# Led_sequencer.net
KiCad netlist of a schematic drawn in Altium Designer
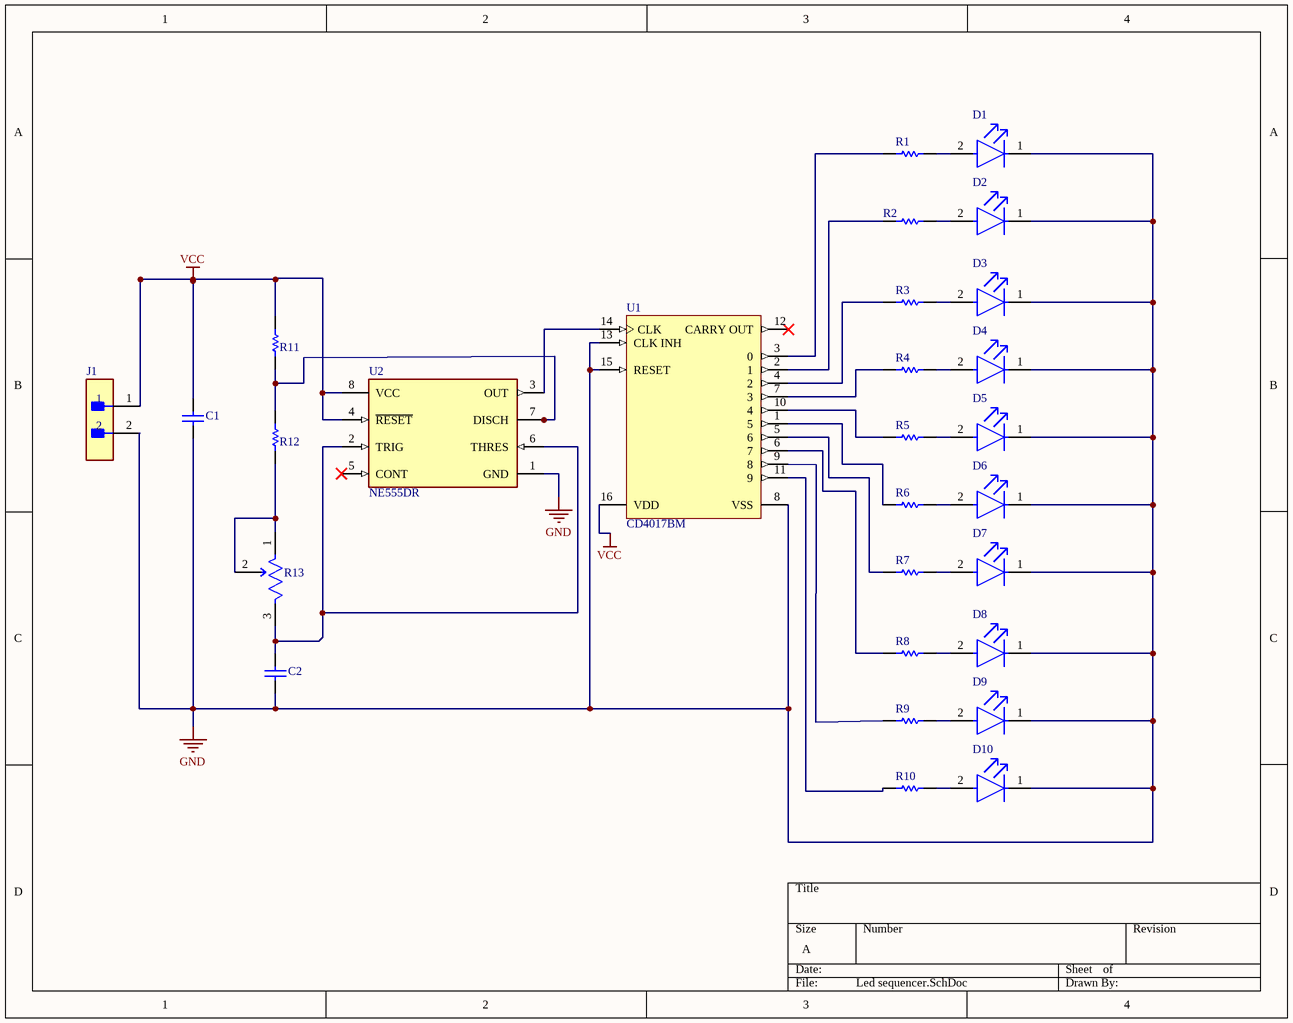
[diagram p0: Led sequencer.SchDoc]

(export (version "E")
  (design (tool "Eeschema 10.0.6"))
  (components
    (comp (ref "C1")
      (value "1uf")
      (footprint "CAPC2013X135X45LL10T25")
      (fields (field (name "MANUFACTURER") "Murata") (field (name "PART NUMBER") "GRM21BR71H105KA12L"))
      (libsource (lib "Altium Content Vault") (part "CAP"))
    )
    (comp (ref "C2")
      (value "1uf")
      (footprint "CAPC2013X135X45LL10T25")
      (fields (field (name "MANUFACTURER") "Murata") (field (name "PART NUMBER") "GRM21BR71H105KA12L"))
      (libsource (lib "Altium Content Vault") (part "CAP"))
    )
    (comp (ref "D1")
      (value "HLMP-1719")
      (footprint "FP-HLMP-1719-MFG")
      (description "LED Uni-Color Yellow 2-Pin T-1")
      (fields (field (name "MANUFACTURER") "Broadcom"))
      (libsource (lib "Altium Content Vault") (part "8706943c75ba83719d021d2fdc84c58"))
    )
    (comp (ref "D2")
      (value "HLMP-1719")
      (footprint "FP-HLMP-1719-MFG")
      (description "LED Uni-Color Yellow 2-Pin T-1")
      (fields (field (name "MANUFACTURER") "Broadcom"))
      (libsource (lib "Altium Content Vault") (part "8706943c75ba83719d021d2fdc84c58"))
    )
    (comp (ref "D3")
      (value "HLMP-1719")
      (footprint "FP-HLMP-1719-MFG")
      (description "LED Uni-Color Yellow 2-Pin T-1")
      (fields (field (name "MANUFACTURER") "Broadcom"))
      (libsource (lib "Altium Content Vault") (part "8706943c75ba83719d021d2fdc84c58"))
    )
    (comp (ref "D4")
      (value "HLMP-1719")
      (footprint "FP-HLMP-1719-MFG")
      (description "LED Uni-Color Yellow 2-Pin T-1")
      (fields (field (name "MANUFACTURER") "Broadcom"))
      (libsource (lib "Altium Content Vault") (part "8706943c75ba83719d021d2fdc84c58"))
    )
    (comp (ref "D5")
      (value "HLMP-1719")
      (footprint "FP-HLMP-1719-MFG")
      (description "LED Uni-Color Yellow 2-Pin T-1")
      (fields (field (name "MANUFACTURER") "Broadcom"))
      (libsource (lib "Altium Content Vault") (part "8706943c75ba83719d021d2fdc84c58"))
    )
    (comp (ref "D6")
      (value "HLMP-1719")
      (footprint "FP-HLMP-1719-MFG")
      (description "LED Uni-Color Yellow 2-Pin T-1")
      (fields (field (name "MANUFACTURER") "Broadcom"))
      (libsource (lib "Altium Content Vault") (part "8706943c75ba83719d021d2fdc84c58"))
    )
    (comp (ref "D7")
      (value "HLMP-1719")
      (footprint "FP-HLMP-1719-MFG")
      (description "LED Uni-Color Yellow 2-Pin T-1")
      (fields (field (name "MANUFACTURER") "Broadcom"))
      (libsource (lib "Altium Content Vault") (part "8706943c75ba83719d021d2fdc84c58"))
    )
    (comp (ref "D8")
      (value "HLMP-1719")
      (footprint "FP-HLMP-1719-MFG")
      (description "LED Uni-Color Yellow 2-Pin T-1")
      (fields (field (name "MANUFACTURER") "Broadcom"))
      (libsource (lib "Altium Content Vault") (part "8706943c75ba83719d021d2fdc84c58"))
    )
    (comp (ref "D9")
      (value "HLMP-1719")
      (footprint "FP-HLMP-1719-MFG")
      (description "LED Uni-Color Yellow 2-Pin T-1")
      (fields (field (name "MANUFACTURER") "Broadcom"))
      (libsource (lib "Altium Content Vault") (part "8706943c75ba83719d021d2fdc84c58"))
    )
    (comp (ref "D10")
      (value "HLMP-1719")
      (footprint "FP-HLMP-1719-MFG")
      (description "LED Uni-Color Yellow 2-Pin T-1")
      (fields (field (name "MANUFACTURER") "Broadcom"))
      (libsource (lib "Altium Content Vault") (part "8706943c75ba83719d021d2fdc84c58"))
    )
    (comp (ref "J1")
      (value "M20-9990246")
      (footprint "FP-M20-9990246-MFG")
      (description "Connector Header Through Hole 2 position 0.100\" (2.54mm)")
      (fields (field (name "OCTOPART") "https://octopart.com/m20-9990246-harwin-2590635"))
      (libsource (lib "Altium Content Vault") (part "3bc925449376181038e59eaffc5286c"))
    )
    (comp (ref "R1")
      (value "1k")
      (footprint "RESC2013X60X35ML10T20")
      (description "Chip Resistor, 1 KOhm, +/- 1%, 125 mW, -55 to 155 degC, 0805 (2012 Metric), RoHS, Tape and Reel")
      (fields (field (name "TOLERANCE") "1%") (field (name "MANUFACTURER") "Yageo"))
      (libsource (lib "Altium Content Vault") (part "RES-2"))
    )
    (comp (ref "R2")
      (value "1k")
      (footprint "RESC2013X60X35ML10T20")
      (description "Chip Resistor, 1 KOhm, +/- 1%, 125 mW, -55 to 155 degC, 0805 (2012 Metric), RoHS, Tape and Reel")
      (fields (field (name "TOLERANCE") "1%") (field (name "MANUFACTURER") "Yageo"))
      (libsource (lib "Altium Content Vault") (part "RES-2"))
    )
    (comp (ref "R3")
      (value "1k")
      (footprint "RESC2013X60X35ML10T20")
      (description "Chip Resistor, 1 KOhm, +/- 1%, 125 mW, -55 to 155 degC, 0805 (2012 Metric), RoHS, Tape and Reel")
      (fields (field (name "TOLERANCE") "1%") (field (name "MANUFACTURER") "Yageo"))
      (libsource (lib "Altium Content Vault") (part "RES-2"))
    )
    (comp (ref "R4")
      (value "1k")
      (footprint "RESC2013X60X35ML10T20")
      (description "Chip Resistor, 1 KOhm, +/- 1%, 125 mW, -55 to 155 degC, 0805 (2012 Metric), RoHS, Tape and Reel")
      (fields (field (name "TOLERANCE") "1%") (field (name "MANUFACTURER") "Yageo"))
      (libsource (lib "Altium Content Vault") (part "RES-2"))
    )
    (comp (ref "R5")
      (value "1k")
      (footprint "RESC2013X60X35ML10T20")
      (description "Chip Resistor, 1 KOhm, +/- 1%, 125 mW, -55 to 155 degC, 0805 (2012 Metric), RoHS, Tape and Reel")
      (fields (field (name "TOLERANCE") "1%") (field (name "MANUFACTURER") "Yageo"))
      (libsource (lib "Altium Content Vault") (part "RES-2"))
    )
    (comp (ref "R6")
      (value "1k")
      (footprint "RESC2013X60X35ML10T20")
      (description "Chip Resistor, 1 KOhm, +/- 1%, 125 mW, -55 to 155 degC, 0805 (2012 Metric), RoHS, Tape and Reel")
      (fields (field (name "TOLERANCE") "1%") (field (name "MANUFACTURER") "Yageo"))
      (libsource (lib "Altium Content Vault") (part "RES-2"))
    )
    (comp (ref "R7")
      (value "1k")
      (footprint "RESC2013X60X35ML10T20")
      (description "Chip Resistor, 1 KOhm, +/- 1%, 125 mW, -55 to 155 degC, 0805 (2012 Metric), RoHS, Tape and Reel")
      (fields (field (name "TOLERANCE") "1%") (field (name "MANUFACTURER") "Yageo"))
      (libsource (lib "Altium Content Vault") (part "RES-2"))
    )
    (comp (ref "R8")
      (value "1k")
      (footprint "RESC2013X60X35ML10T20")
      (description "Chip Resistor, 1 KOhm, +/- 1%, 125 mW, -55 to 155 degC, 0805 (2012 Metric), RoHS, Tape and Reel")
      (fields (field (name "TOLERANCE") "1%") (field (name "MANUFACTURER") "Yageo"))
      (libsource (lib "Altium Content Vault") (part "RES-2"))
    )
    (comp (ref "R9")
      (value "1k")
      (footprint "RESC2013X60X35ML10T20")
      (description "Chip Resistor, 1 KOhm, +/- 1%, 125 mW, -55 to 155 degC, 0805 (2012 Metric), RoHS, Tape and Reel")
      (fields (field (name "TOLERANCE") "1%") (field (name "MANUFACTURER") "Yageo"))
      (libsource (lib "Altium Content Vault") (part "RES-2"))
    )
    (comp (ref "R10")
      (value "1k")
      (footprint "RESC2013X60X35ML10T20")
      (description "Chip Resistor, 1 KOhm, +/- 1%, 125 mW, -55 to 155 degC, 0805 (2012 Metric), RoHS, Tape and Reel")
      (fields (field (name "TOLERANCE") "1%") (field (name "MANUFACTURER") "Yageo"))
      (libsource (lib "Altium Content Vault") (part "RES-2"))
    )
    (comp (ref "R11")
      (value "2.2k")
      (footprint "RESC2013X60X35ML10T20")
      (description "Chip Resistor, 1 KOhm, +/- 1%, 125 mW, -55 to 155 degC, 0805 (2012 Metric), RoHS, Tape and Reel")
      (fields (field (name "TOLERANCE") "1%") (field (name "MANUFACTURER") "Yageo"))
      (libsource (lib "Altium Content Vault") (part "RES-2"))
    )
    (comp (ref "R12")
      (value "10k")
      (footprint "RESC2013X60X35ML10T20")
      (description "Chip Resistor, 1 KOhm, +/- 1%, 125 mW, -55 to 155 degC, 0805 (2012 Metric), RoHS, Tape and Reel")
      (fields (field (name "TOLERANCE") "1%") (field (name "MANUFACTURER") "Yageo"))
      (libsource (lib "Altium Content Vault") (part "RES-2"))
    )
    (comp (ref "R13")
      (value "50k")
      (footprint "FP-3386P-MFG")
      (description "TRIMMER 100K OHM 0.5W PC PIN TOP")
      (fields (field (name "TOLERANCE") "10%"))
      (libsource (lib "Altium Content Vault") (part "13357d81287629c2fd191d242cfa50c"))
    )
    (comp (ref "U1")
      (value "CD4017BM")
      (footprint "D0016A_N")
      (description "CMOS Decade Counter with 10 Decoded Outputs, D0016A, TUBE")
      (fields
        (field (name "GENERIC PART NUMBER") "CD4017B")
        (field (name "MANUFACTURER") "Texas Instruments")
      )
      (libsource (lib "Altium Content Vault") (part "TI-CD4017B-16"))
    )
    (comp (ref "U2")
      (value "NE555DR")
      (footprint "FP-D0008A-IPC_A")
      (description "IC OSC SGL TIMER 100KHZ 8-SOIC")
      (libsource (lib "Altium Content Vault") (part "a29bba90211dec1890110b94dad7d53"))
    )
  )
  (nets
    (net (code "1") (name "GND") (class "Default")
      (node (ref "C1") (pin "1") (pinfunction "1_1") (pintype "passive"))
      (node (ref "C2") (pin "1") (pinfunction "1_1") (pintype "passive"))
      (node (ref "D1") (pin "1") (pinfunction "C_1") (pintype "passive"))
      (node (ref "D10") (pin "1") (pinfunction "C_1") (pintype "passive"))
      (node (ref "D2") (pin "1") (pinfunction "C_1") (pintype "passive"))
      (node (ref "D3") (pin "1") (pinfunction "C_1") (pintype "passive"))
      (node (ref "D4") (pin "1") (pinfunction "C_1") (pintype "passive"))
      (node (ref "D5") (pin "1") (pinfunction "C_1") (pintype "passive"))
      (node (ref "D6") (pin "1") (pinfunction "C_1") (pintype "passive"))
      (node (ref "D7") (pin "1") (pinfunction "C_1") (pintype "passive"))
      (node (ref "D8") (pin "1") (pinfunction "C_1") (pintype "passive"))
      (node (ref "D9") (pin "1") (pinfunction "C_1") (pintype "passive"))
      (node (ref "J1") (pin "2") (pinfunction "2_2") (pintype "passive"))
      (node (ref "U1") (pin "13") (pinfunction "CLK_INH_13") (pintype "input"))
      (node (ref "U1") (pin "15") (pinfunction "RESET_15") (pintype "input"))
      (node (ref "U1") (pin "8") (pinfunction "VSS_8") (pintype "power_in"))
      (node (ref "U2") (pin "1") (pinfunction "GND_1") (pintype "power_in"))
    )
    (net (code "2") (name "Net-(D1-A)") (class "Default")
      (node (ref "D1") (pin "2") (pinfunction "A_2") (pintype "passive"))
      (node (ref "R1") (pin "2") (pinfunction "2_2") (pintype "passive"))
    )
    (net (code "3") (name "Net-(D2-A)") (class "Default")
      (node (ref "D2") (pin "2") (pinfunction "A_2") (pintype "passive"))
      (node (ref "R2") (pin "2") (pinfunction "2_2") (pintype "passive"))
    )
    (net (code "4") (name "Net-(D3-A)") (class "Default")
      (node (ref "D3") (pin "2") (pinfunction "A_2") (pintype "passive"))
      (node (ref "R3") (pin "2") (pinfunction "2_2") (pintype "passive"))
    )
    (net (code "5") (name "Net-(D4-A)") (class "Default")
      (node (ref "D4") (pin "2") (pinfunction "A_2") (pintype "passive"))
      (node (ref "R4") (pin "2") (pinfunction "2_2") (pintype "passive"))
    )
    (net (code "6") (name "Net-(D5-A)") (class "Default")
      (node (ref "D5") (pin "2") (pinfunction "A_2") (pintype "passive"))
      (node (ref "R5") (pin "2") (pinfunction "2_2") (pintype "passive"))
    )
    (net (code "7") (name "Net-(D6-A)") (class "Default")
      (node (ref "D6") (pin "2") (pinfunction "A_2") (pintype "passive"))
      (node (ref "R6") (pin "2") (pinfunction "2_2") (pintype "passive"))
    )
    (net (code "8") (name "Net-(D7-A)") (class "Default")
      (node (ref "D7") (pin "2") (pinfunction "A_2") (pintype "passive"))
      (node (ref "R7") (pin "2") (pinfunction "2_2") (pintype "passive"))
    )
    (net (code "9") (name "Net-(D8-A)") (class "Default")
      (node (ref "D8") (pin "2") (pinfunction "A_2") (pintype "passive"))
      (node (ref "R8") (pin "2") (pinfunction "2_2") (pintype "passive"))
    )
    (net (code "10") (name "Net-(D9-A)") (class "Default")
      (node (ref "D9") (pin "2") (pinfunction "A_2") (pintype "passive"))
      (node (ref "R9") (pin "2") (pinfunction "2_2") (pintype "passive"))
    )
    (net (code "11") (name "Net-(D10-A)") (class "Default")
      (node (ref "D10") (pin "2") (pinfunction "A_2") (pintype "passive"))
      (node (ref "R10") (pin "2") (pinfunction "2_2") (pintype "passive"))
    )
    (net (code "12") (name "Net-(R13-CCW)") (class "Default")
      (node (ref "R12") (pin "1") (pinfunction "1_1") (pintype "passive"))
      (node (ref "R13") (pin "1") (pinfunction "CCW_1") (pintype "passive"))
      (node (ref "R13") (pin "2") (pinfunction "WIPER_2") (pintype "passive"))
    )
    (net (code "13") (name "Net-(R13-CW)") (class "Default")
      (node (ref "C2") (pin "2") (pinfunction "2_2") (pintype "passive"))
      (node (ref "R13") (pin "3") (pinfunction "CW_3") (pintype "passive"))
      (node (ref "U2") (pin "2") (pinfunction "TRIG_2") (pintype "input"))
      (node (ref "U2") (pin "6") (pinfunction "THRES_6") (pintype "input"))
    )
    (net (code "14") (name "Net-(U1-0)") (class "Default")
      (node (ref "R1") (pin "1") (pinfunction "1_1") (pintype "passive"))
      (node (ref "U1") (pin "3") (pinfunction "0_3") (pintype "output"))
    )
    (net (code "15") (name "Net-(U1-1)") (class "Default")
      (node (ref "R2") (pin "1") (pinfunction "1_1") (pintype "passive"))
      (node (ref "U1") (pin "2") (pinfunction "1_2") (pintype "output"))
    )
    (net (code "16") (name "Net-(U1-2)") (class "Default")
      (node (ref "R3") (pin "1") (pinfunction "1_1") (pintype "passive"))
      (node (ref "U1") (pin "4") (pinfunction "2_4") (pintype "output"))
    )
    (net (code "17") (name "Net-(U1-3)") (class "Default")
      (node (ref "R4") (pin "1") (pinfunction "1_1") (pintype "passive"))
      (node (ref "U1") (pin "7") (pinfunction "3_7") (pintype "output"))
    )
    (net (code "18") (name "Net-(U1-4)") (class "Default")
      (node (ref "R5") (pin "1") (pinfunction "1_1") (pintype "passive"))
      (node (ref "U1") (pin "10") (pinfunction "4_10") (pintype "output"))
    )
    (net (code "19") (name "Net-(U1-5)") (class "Default")
      (node (ref "R6") (pin "1") (pinfunction "1_1") (pintype "passive"))
      (node (ref "U1") (pin "1") (pinfunction "5_1") (pintype "output"))
    )
    (net (code "20") (name "Net-(U1-6)") (class "Default")
      (node (ref "R7") (pin "1") (pinfunction "1_1") (pintype "passive"))
      (node (ref "U1") (pin "5") (pinfunction "6_5") (pintype "output"))
    )
    (net (code "21") (name "Net-(U1-7)") (class "Default")
      (node (ref "R8") (pin "1") (pinfunction "1_1") (pintype "passive"))
      (node (ref "U1") (pin "6") (pinfunction "7_6") (pintype "output"))
    )
    (net (code "22") (name "Net-(U1-8)") (class "Default")
      (node (ref "R9") (pin "1") (pinfunction "1_1") (pintype "passive"))
      (node (ref "U1") (pin "9") (pinfunction "8_9") (pintype "output"))
    )
    (net (code "23") (name "Net-(U1-9)") (class "Default")
      (node (ref "R10") (pin "1") (pinfunction "1_1") (pintype "passive"))
      (node (ref "U1") (pin "11") (pinfunction "9_11") (pintype "output"))
    )
    (net (code "24") (name "Net-(U1-CLK)") (class "Default")
      (node (ref "U1") (pin "14") (pinfunction "CLK_14") (pintype "input"))
      (node (ref "U2") (pin "3") (pinfunction "OUT_3") (pintype "output"))
    )
    (net (code "25") (name "Net-(U2-DISCH)") (class "Default")
      (node (ref "R11") (pin "1") (pinfunction "1_1") (pintype "passive"))
      (node (ref "R12") (pin "2") (pinfunction "2_2") (pintype "passive"))
      (node (ref "U2") (pin "7") (pinfunction "DISCH_7") (pintype "open_collector"))
    )
    (net (code "26") (name "VCC") (class "Default")
      (node (ref "C1") (pin "2") (pinfunction "2_2") (pintype "passive"))
      (node (ref "J1") (pin "1") (pinfunction "1_1") (pintype "passive"))
      (node (ref "R11") (pin "2") (pinfunction "2_2") (pintype "passive"))
      (node (ref "U1") (pin "16") (pinfunction "VDD_16") (pintype "power_in"))
      (node (ref "U2") (pin "4") (pinfunction "~{RESET}_4") (pintype "input"))
      (node (ref "U2") (pin "8") (pinfunction "VCC_8") (pintype "power_in"))
    )
    (net (code "27") (name "unconnected-(U1-CARRY_OUT-Pad12)") (class "Default")
      (node (ref "U1") (pin "12") (pinfunction "CARRY_OUT_12") (pintype "output+no_connect"))
    )
    (net (code "28") (name "unconnected-(U2-CONT-Pad5)") (class "Default")
      (node (ref "U2") (pin "5") (pinfunction "CONT_5") (pintype "input+no_connect"))
    )
  )
)
